# ManitoBoardFinal.net
KiCad netlist of a schematic drawn in EAGLE
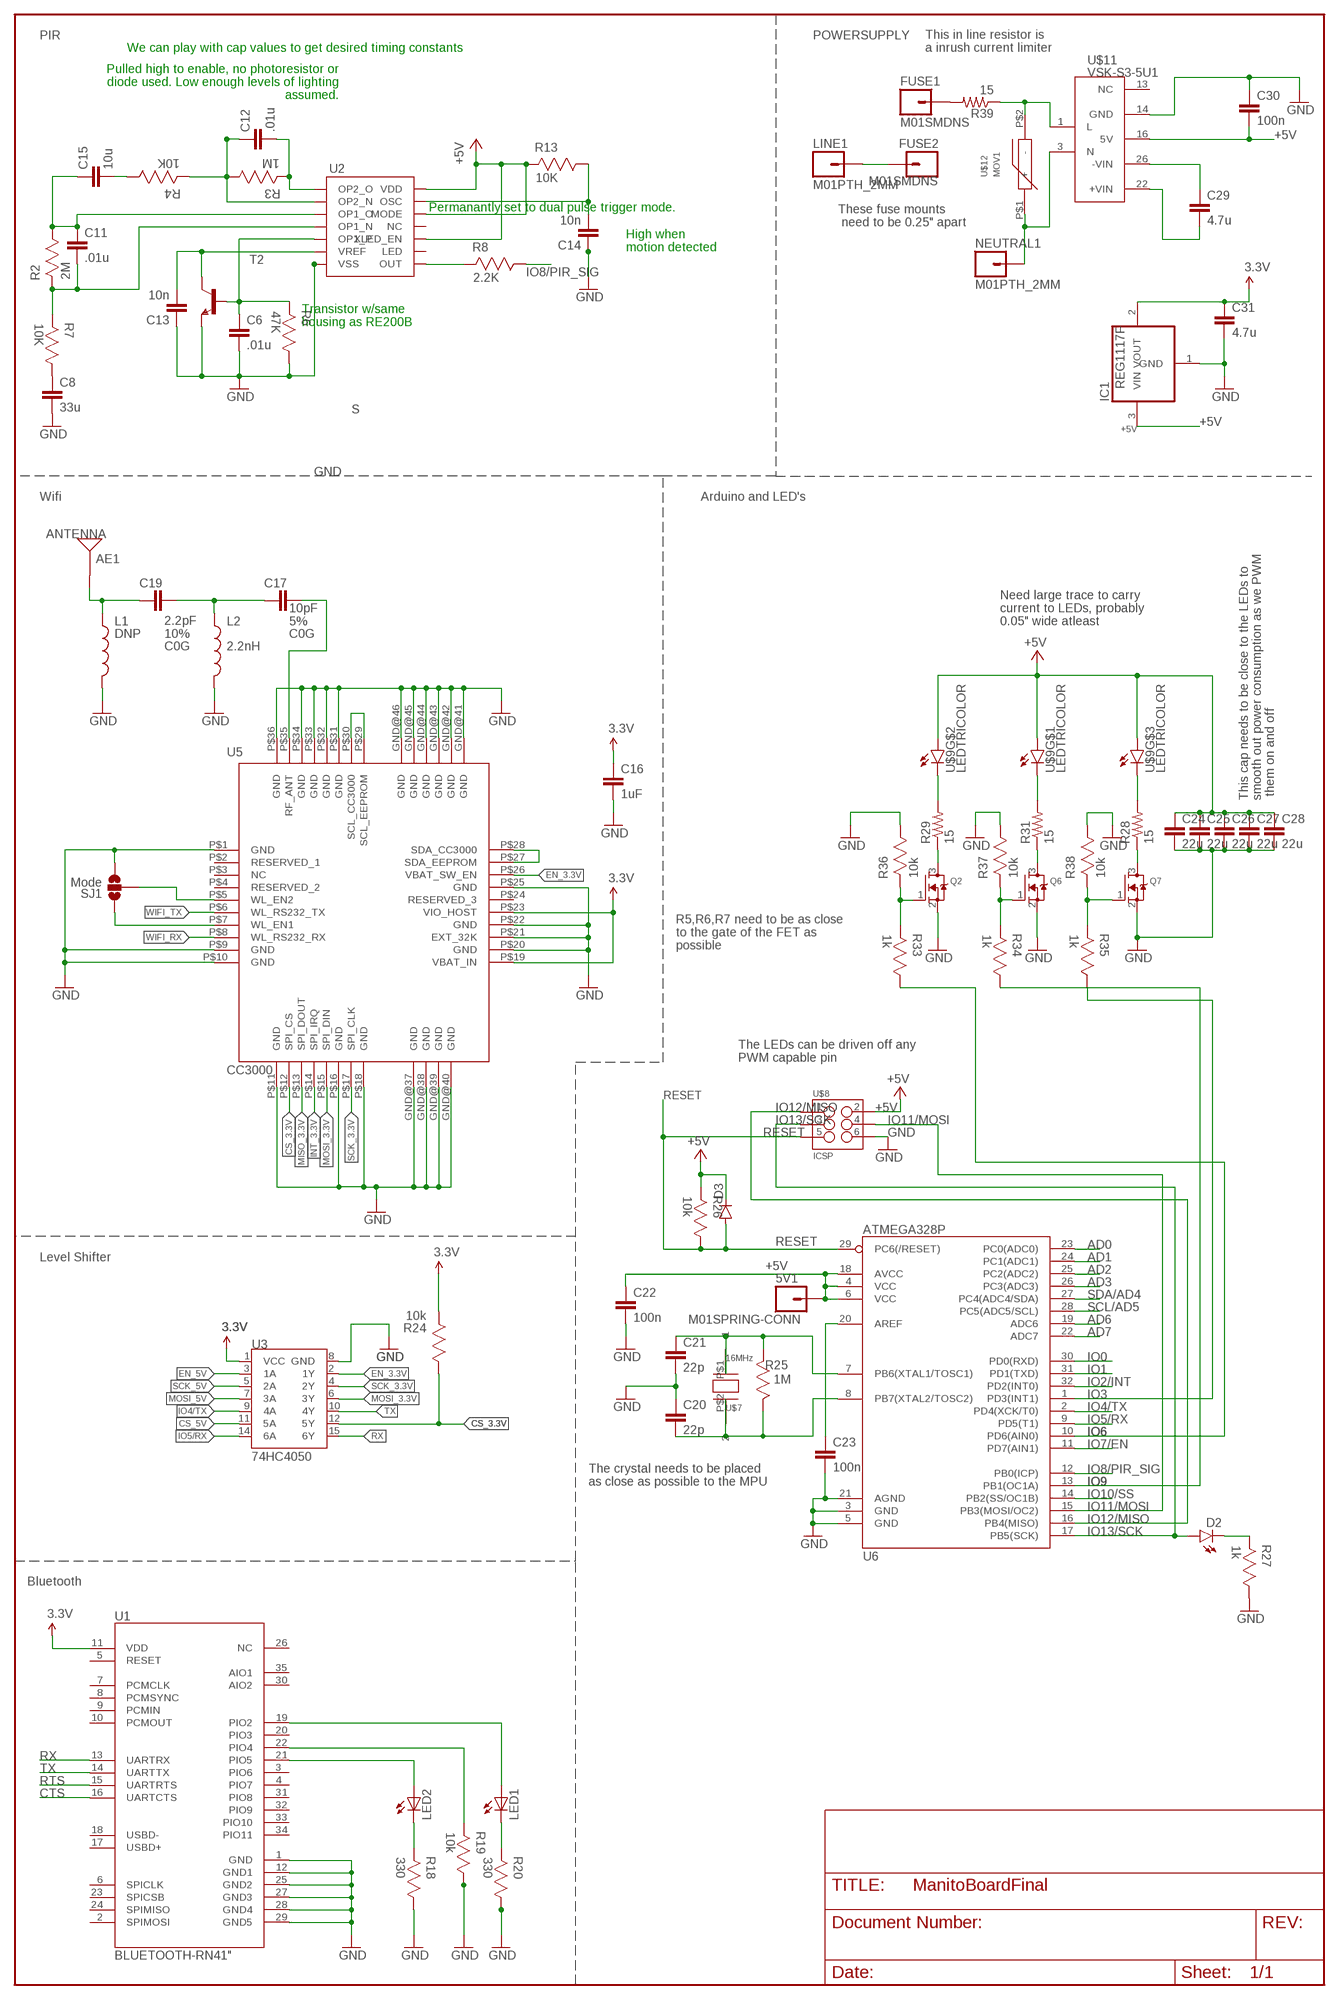
[diagram p0: schematic, sheet 1]

(export (version "E")
  (design (tool "Eeschema 10.0.6"))
  (components
    (comp (ref "5V1")
      (value "M01SPRING-CONN")
      (footprint "eagle-import:SPRING-CONNECTOR")
      (libsource (lib "eagle-import") (part "M01SPRING-CONN"))
    )
    (comp (ref "AE1")
      (value "ANTENNA")
      (footprint "eagle-import:ANTENNA-CHIP_2500AT44M0400")
      (libsource (lib "eagle-import") (part "ANTENNA22500AT44M0400"))
    )
    (comp (ref "C6")
      (value ".01u")
      (footprint "eagle-import:0805")
      (libsource (lib "eagle-import") (part "CAP0805"))
    )
    (comp (ref "C8")
      (value "33u")
      (footprint "eagle-import:0805")
      (libsource (lib "eagle-import") (part "CAP0805"))
    )
    (comp (ref "C11")
      (value ".01u")
      (footprint "eagle-import:0805")
      (libsource (lib "eagle-import") (part "CAP0805"))
    )
    (comp (ref "C12")
      (value ".01u")
      (footprint "eagle-import:0805")
      (libsource (lib "eagle-import") (part "CAP0805"))
    )
    (comp (ref "C13")
      (value "10n")
      (footprint "eagle-import:0805")
      (libsource (lib "eagle-import") (part "CAP0805"))
    )
    (comp (ref "C14")
      (value "10n")
      (footprint "eagle-import:0805")
      (libsource (lib "eagle-import") (part "CAP0805"))
    )
    (comp (ref "C15")
      (value "10u")
      (footprint "eagle-import:0805")
      (libsource (lib "eagle-import") (part "CAP0805"))
    )
    (comp (ref "C16")
      (value "1uF")
      (footprint "eagle-import:0805")
      (libsource (lib "eagle-import") (part "SparkFun-Capacitors_CAP0805"))
    )
    (comp (ref "C17")
      (value "10pF")
      (footprint "eagle-import:0603-CAP")
      (fields (field (name "COEFF") "C0G") (field (name "TOL") "5%"))
      (libsource (lib "eagle-import") (part "SparkFun-Capacitors_CAP0603-CAP"))
    )
    (comp (ref "C19")
      (value "2.2pF")
      (footprint "eagle-import:0603-CAP")
      (fields (field (name "COEFF") "C0G") (field (name "TOL") "10%"))
      (libsource (lib "eagle-import") (part "SparkFun-Capacitors_CAP0603-CAP"))
    )
    (comp (ref "C20")
      (value "22p")
      (footprint "eagle-import:0603-CAP")
      (libsource (lib "eagle-import") (part "CAP0603-CAP"))
    )
    (comp (ref "C21")
      (value "22p")
      (footprint "eagle-import:0603-CAP")
      (libsource (lib "eagle-import") (part "CAP0603-CAP"))
    )
    (comp (ref "C22")
      (value "100n")
      (footprint "eagle-import:0603-CAP")
      (libsource (lib "eagle-import") (part "CAP0603-CAP"))
    )
    (comp (ref "C23")
      (value "100n")
      (footprint "eagle-import:0603-CAP")
      (libsource (lib "eagle-import") (part "CAP0603-CAP"))
    )
    (comp (ref "C24")
      (value "22u")
      (footprint "eagle-import:0603-CAP")
      (libsource (lib "eagle-import") (part "CAP0603-CAP"))
    )
    (comp (ref "C25")
      (value "22u")
      (footprint "eagle-import:0603-CAP")
      (libsource (lib "eagle-import") (part "CAP0603-CAP"))
    )
    (comp (ref "C26")
      (value "22u")
      (footprint "eagle-import:0603-CAP")
      (libsource (lib "eagle-import") (part "CAP0603-CAP"))
    )
    (comp (ref "C27")
      (value "22u")
      (footprint "eagle-import:0603-CAP")
      (libsource (lib "eagle-import") (part "CAP0603-CAP"))
    )
    (comp (ref "C28")
      (value "22u")
      (footprint "eagle-import:0603-CAP")
      (libsource (lib "eagle-import") (part "CAP0603-CAP"))
    )
    (comp (ref "C29")
      (value "4.7u")
      (footprint "eagle-import:AXIAL-5MM")
      (libsource (lib "eagle-import") (part "CAP_"))
    )
    (comp (ref "C30")
      (value "100n")
      (footprint "eagle-import:0603-CAP")
      (libsource (lib "eagle-import") (part "CAP0603-CAP"))
    )
    (comp (ref "C31")
      (value "4.7u")
      (footprint "eagle-import:0603-CAP")
      (libsource (lib "eagle-import") (part "CAP0603-CAP"))
    )
    (comp (ref "D2")
      (value "LED-YELLOW0603")
      (footprint "eagle-import:LED-0603")
      (libsource (lib "eagle-import") (part "LED-YELLOW0603"))
    )
    (comp (ref "D3")
      (value "DIODESOD123")
      (footprint "eagle-import:SOD-123")
      (libsource (lib "eagle-import") (part "DIODESOD123"))
    )
    (comp (ref "FUSE1")
      (value "M01SMDNS")
      (footprint "eagle-import:1X01NS")
      (libsource (lib "eagle-import") (part "M01SMDNS"))
    )
    (comp (ref "FUSE2")
      (value "M01SMDNS")
      (footprint "eagle-import:1X01NS")
      (libsource (lib "eagle-import") (part "M01SMDNS"))
    )
    (comp (ref "IC1")
      (value "REG1117F")
      (footprint "eagle-import:DD-3")
      (fields (field (name "MF") "TEXAS INSTRUMENTS") (field (name "MPN") "REG1117FAKTTT"))
      (libsource (lib "eagle-import") (part "REG1117F"))
    )
    (comp (ref "L1")
      (value "DNP")
      (footprint "eagle-import:0603")
      (libsource (lib "eagle-import") (part "INDUCTOR0603"))
    )
    (comp (ref "L2")
      (value "2.2nH")
      (footprint "eagle-import:0603")
      (libsource (lib "eagle-import") (part "INDUCTOR0603"))
    )
    (comp (ref "LED1")
      (value "LED_ESML0603")
      (footprint "eagle-import:LED_SML0603")
      (libsource (lib "eagle-import") (part "LED_ESML0603"))
    )
    (comp (ref "LED2")
      (value "LED_ESML0603")
      (footprint "eagle-import:LED_SML0603")
      (libsource (lib "eagle-import") (part "LED_ESML0603"))
    )
    (comp (ref "LINE1")
      (value "M01PTH_2MM")
      (footprint "eagle-import:1X01_2MM")
      (libsource (lib "eagle-import") (part "M01PTH_2MM"))
    )
    (comp (ref "NEUTRAL1")
      (value "M01PTH_2MM")
      (footprint "eagle-import:1X01_2MM")
      (libsource (lib "eagle-import") (part "M01PTH_2MM"))
    )
    (comp (ref "Q2")
      (value "MOSFET-NREFLOW")
      (footprint "eagle-import:SOT23")
      (libsource (lib "eagle-import") (part "MOSFET-NREFLOW"))
    )
    (comp (ref "Q6")
      (value "MOSFET-NREFLOW")
      (footprint "eagle-import:SOT23")
      (libsource (lib "eagle-import") (part "MOSFET-NREFLOW"))
    )
    (comp (ref "Q7")
      (value "MOSFET-NREFLOW")
      (footprint "eagle-import:SOT23")
      (libsource (lib "eagle-import") (part "MOSFET-NREFLOW"))
    )
    (comp (ref "R2")
      (value "2M")
      (footprint "eagle-import:0603RESISTOR")
      (fields (field (name "MPN") "CRCW06031K21FKEA") (field (name "TOLERANCE") "± 1.0 %"))
      (libsource (lib "eagle-import") (part "0603RESISTOR1"))
    )
    (comp (ref "R3")
      (value "1M")
      (footprint "eagle-import:0603RESISTOR")
      (fields (field (name "MPN") "CRCW06031K21FKEA") (field (name "TOLERANCE") "± 1.0 %"))
      (libsource (lib "eagle-import") (part "0603RESISTOR1"))
    )
    (comp (ref "R4")
      (value "10K")
      (footprint "eagle-import:0603RESISTOR")
      (fields (field (name "MPN") "CRCW06031K21FKEA") (field (name "TOLERANCE") "± 1.0 %"))
      (libsource (lib "eagle-import") (part "0603RESISTOR1"))
    )
    (comp (ref "R6")
      (value "47K")
      (footprint "eagle-import:0603RESISTOR")
      (fields (field (name "MPN") "CRCW06031K21FKEA") (field (name "TOLERANCE") "± 1.0 %"))
      (libsource (lib "eagle-import") (part "0603RESISTOR1"))
    )
    (comp (ref "R7")
      (value "10K")
      (footprint "eagle-import:0603RESISTOR")
      (fields (field (name "MPN") "CRCW06031K21FKEA") (field (name "TOLERANCE") "± 1.0 %"))
      (libsource (lib "eagle-import") (part "0603RESISTOR1"))
    )
    (comp (ref "R8")
      (value "2.2K")
      (footprint "eagle-import:0603RESISTOR")
      (fields (field (name "MPN") "CRCW06031K21FKEA") (field (name "TOLERANCE") "± 1.0 %"))
      (libsource (lib "eagle-import") (part "0603RESISTOR1"))
    )
    (comp (ref "R13")
      (value "10K")
      (footprint "eagle-import:0603RESISTOR")
      (fields (field (name "MPN") "CRCW06031K21FKEA") (field (name "TOLERANCE") "± 1.0 %"))
      (libsource (lib "eagle-import") (part "0603RESISTOR1"))
    )
    (comp (ref "R18")
      (value "330")
      (footprint "eagle-import:0603RESISTOR")
      (fields (field (name "MPN") "CRCW06031K21FKEA") (field (name "TOLERANCE") "± 1.0 %"))
      (libsource (lib "eagle-import") (part "0603RESISTOR1"))
    )
    (comp (ref "R19")
      (value "10k")
      (footprint "eagle-import:0603RESISTOR")
      (fields (field (name "MPN") "CRCW06031K21FKEA") (field (name "TOLERANCE") "± 1.0 %"))
      (libsource (lib "eagle-import") (part "0603RESISTOR1"))
    )
    (comp (ref "R20")
      (value "330")
      (footprint "eagle-import:0603RESISTOR")
      (fields (field (name "MPN") "CRCW06031K21FKEA") (field (name "TOLERANCE") "± 1.0 %"))
      (libsource (lib "eagle-import") (part "0603RESISTOR1"))
    )
    (comp (ref "R24")
      (value "10k")
      (footprint "eagle-import:0603RESISTOR")
      (fields (field (name "MPN") "CRCW06031K21FKEA") (field (name "TOLERANCE") "± 1.0 %"))
      (libsource (lib "eagle-import") (part "0603RESISTOR1"))
    )
    (comp (ref "R25")
      (value "1M")
      (footprint "eagle-import:0603RESISTOR")
      (fields (field (name "MPN") "CRCW06031K21FKEA") (field (name "TOLERANCE") "± 1.0 %"))
      (libsource (lib "eagle-import") (part "0603RESISTOR1"))
    )
    (comp (ref "R26")
      (value "10k")
      (footprint "eagle-import:0603RESISTOR")
      (fields (field (name "MPN") "CRCW06031K21FKEA") (field (name "TOLERANCE") "± 1.0 %"))
      (libsource (lib "eagle-import") (part "0603RESISTOR1"))
    )
    (comp (ref "R27")
      (value "1k")
      (footprint "eagle-import:0603RESISTOR")
      (fields (field (name "MPN") "CRCW06031K21FKEA") (field (name "TOLERANCE") "± 1.0 %"))
      (libsource (lib "eagle-import") (part "0603RESISTOR1"))
    )
    (comp (ref "R28")
      (value "15")
      (footprint "eagle-import:AXIAL-0.6")
      (libsource (lib "eagle-import") (part "RESISTORPTH-1W"))
    )
    (comp (ref "R29")
      (value "15")
      (footprint "eagle-import:AXIAL-0.6")
      (libsource (lib "eagle-import") (part "RESISTORPTH-1W"))
    )
    (comp (ref "R31")
      (value "15")
      (footprint "eagle-import:AXIAL-0.6")
      (libsource (lib "eagle-import") (part "RESISTORPTH-1W"))
    )
    (comp (ref "R33")
      (value "1k")
      (footprint "eagle-import:0603RESISTOR")
      (fields (field (name "MPN") "CRCW06031K21FKEA") (field (name "TOLERANCE") "± 1.0 %"))
      (libsource (lib "eagle-import") (part "0603RESISTOR1"))
    )
    (comp (ref "R34")
      (value "1k")
      (footprint "eagle-import:0603RESISTOR")
      (fields (field (name "MPN") "CRCW06031K21FKEA") (field (name "TOLERANCE") "± 1.0 %"))
      (libsource (lib "eagle-import") (part "0603RESISTOR1"))
    )
    (comp (ref "R35")
      (value "1k")
      (footprint "eagle-import:0603RESISTOR")
      (fields (field (name "MPN") "CRCW06031K21FKEA") (field (name "TOLERANCE") "± 1.0 %"))
      (libsource (lib "eagle-import") (part "0603RESISTOR1"))
    )
    (comp (ref "R36")
      (value "10k")
      (footprint "eagle-import:0603RESISTOR")
      (fields (field (name "MPN") "CRCW06031K21FKEA") (field (name "TOLERANCE") "± 1.0 %"))
      (libsource (lib "eagle-import") (part "0603RESISTOR1"))
    )
    (comp (ref "R37")
      (value "10k")
      (footprint "eagle-import:0603RESISTOR")
      (fields (field (name "MPN") "CRCW06031K21FKEA") (field (name "TOLERANCE") "± 1.0 %"))
      (libsource (lib "eagle-import") (part "0603RESISTOR1"))
    )
    (comp (ref "R38")
      (value "10k")
      (footprint "eagle-import:0603RESISTOR")
      (fields (field (name "MPN") "CRCW06031K21FKEA") (field (name "TOLERANCE") "± 1.0 %"))
      (libsource (lib "eagle-import") (part "0603RESISTOR1"))
    )
    (comp (ref "R39")
      (value "15")
      (footprint "eagle-import:AXIAL-0.6")
      (libsource (lib "eagle-import") (part "RESISTORPTH-1W"))
    )
    (comp (ref "SJ1")
      (value "Mode")
      (footprint "eagle-import:SJ_3_PASTE1&2")
      (libsource (lib "eagle-import") (part "SOLDERJUMPER_2WAYPASTE1&2"))
    )
    (comp (ref "T2")
      (value "-NPN-TO5")
      (footprint "eagle-import:TO5")
      (libsource (lib "eagle-import") (part "-NPN-TO5"))
    )
    (comp (ref "U$7")
      (value "16MHz")
      (footprint "eagle-import:SMDCRYSTAL")
      (libsource (lib "eagle-import") (part "SMDCRYSTAL"))
    )
    (comp (ref "U$8")
      (value "ICSP")
      (footprint "eagle-import:2X3-ICSP")
      (libsource (lib "eagle-import") (part "6PIN-ICSP"))
    )
    (comp (ref "U$9")
      (value "LEDTRICOLOR")
      (footprint "eagle-import:TRICOLORLED")
      (libsource (lib "eagle-import") (part "LEDTRICOLOR"))
    )
    (comp (ref "U$11")
      (value "VSK-S3-5U1")
      (footprint "eagle-import:VSK-S3-DCAC")
      (libsource (lib "eagle-import") (part "VSK-S3-5U1"))
    )
    (comp (ref "U$12")
      (value "MOV1")
      (footprint "eagle-import:MOV")
      (libsource (lib "eagle-import") (part "MOV1"))
    )
    (comp (ref "U1")
      (value "BLUETOOTH-RN41\"")
      (footprint "eagle-import:RN41")
      (libsource (lib "eagle-import") (part "BLUETOOTH-RN41{dblquote}"))
    )
    (comp (ref "U2")
      (value "NCS36000")
      (footprint "eagle-import:SO14")
      (libsource (lib "eagle-import") (part "NCS36000"))
    )
    (comp (ref "U3")
      (value "74HC4050")
      (footprint "eagle-import:SO016")
      (libsource (lib "eagle-import") (part "HEX_CONVERTER"))
    )
    (comp (ref "U5")
      (value "CC3000")
      (footprint "eagle-import:QFN-46_CC3000")
      (libsource (lib "eagle-import") (part "CC3000"))
    )
    (comp (ref "U6")
      (value "ATMEGA328P")
      (footprint "eagle-import:TQFP32-08")
      (libsource (lib "eagle-import") (part "ATMEGA328_SMT"))
    )
  )
  (nets
    (net (code "1") (name "+5V") (class "Default")
      (node (ref "5V1") (pin "P$2") (pinfunction "1_P$2") (pintype "passive"))
      (node (ref "C22") (pin "1") (pinfunction "1_1") (pintype "passive"))
      (node (ref "C24") (pin "1") (pinfunction "1_1") (pintype "passive"))
      (node (ref "C25") (pin "1") (pinfunction "1_1") (pintype "passive"))
      (node (ref "C26") (pin "1") (pinfunction "1_1") (pintype "passive"))
      (node (ref "C27") (pin "1") (pinfunction "1_1") (pintype "passive"))
      (node (ref "C28") (pin "1") (pinfunction "1_1") (pintype "passive"))
      (node (ref "C30") (pin "2") (pinfunction "2_2") (pintype "passive"))
      (node (ref "D3") (pin "C") (pinfunction "C_C") (pintype "passive"))
      (node (ref "IC1") (pin "3") (pinfunction "VIN_3") (pintype "input"))
      (node (ref "R13") (pin "2") (pinfunction "2_2") (pintype "passive"))
      (node (ref "R26") (pin "2") (pinfunction "2_2") (pintype "passive"))
      (node (ref "U$11") (pin "16") (pinfunction "5V_16") (pintype "bidirectional"))
      (node (ref "U$8") (pin "2") (pinfunction "+5V_2") (pintype "power_in"))
      (node (ref "U$9") (pin "A1") (pinfunction "A_A1") (pintype "passive"))
      (node (ref "U$9") (pin "A2") (pinfunction "A_A2") (pintype "passive"))
      (node (ref "U$9") (pin "A3") (pinfunction "A_A3") (pintype "passive"))
      (node (ref "U2") (pin "10") (pinfunction "XLED_EN_10") (pintype "bidirectional"))
      (node (ref "U2") (pin "12") (pinfunction "MODE_12") (pintype "bidirectional"))
      (node (ref "U2") (pin "14") (pinfunction "VDD_14") (pintype "power_in"))
      (node (ref "U6") (pin "18") (pinfunction "AVCC_18") (pintype "bidirectional"))
      (node (ref "U6") (pin "4") (pinfunction "VCC_4") (pintype "bidirectional"))
      (node (ref "U6") (pin "6") (pinfunction "VCC_6") (pintype "bidirectional"))
    )
    (net (code "2") (name "/AD0") (class "Default")
      (node (ref "U6") (pin "23") (pinfunction "PC0(ADC0)_23") (pintype "bidirectional"))
    )
    (net (code "3") (name "/AD1") (class "Default")
      (node (ref "U6") (pin "24") (pinfunction "PC1(ADC1)_24") (pintype "bidirectional"))
    )
    (net (code "4") (name "/AD2") (class "Default")
      (node (ref "U6") (pin "25") (pinfunction "PC2(ADC2)_25") (pintype "bidirectional"))
    )
    (net (code "5") (name "/AD3") (class "Default")
      (node (ref "U6") (pin "26") (pinfunction "PC3(ADC3)_26") (pintype "bidirectional"))
    )
    (net (code "6") (name "/AD6") (class "Default")
      (node (ref "U6") (pin "19") (pinfunction "ADC6_19") (pintype "bidirectional"))
    )
    (net (code "7") (name "/AD7") (class "Default")
      (node (ref "U6") (pin "22") (pinfunction "ADC7_22") (pintype "bidirectional"))
    )
    (net (code "8") (name "/CTS") (class "Default")
      (node (ref "U1") (pin "16") (pinfunction "UARTCTS_16") (pintype "bidirectional"))
    )
    (net (code "9") (name "/IO0") (class "Default")
      (node (ref "U6") (pin "30") (pinfunction "PD0(RXD)_30") (pintype "bidirectional"))
    )
    (net (code "10") (name "/IO1") (class "Default")
      (node (ref "U6") (pin "31") (pinfunction "PD1(TXD)_31") (pintype "bidirectional"))
    )
    (net (code "11") (name "/IO2{slash}INT") (class "Default")
      (node (ref "U6") (pin "32") (pinfunction "PD2(INT0)_32") (pintype "bidirectional"))
    )
    (net (code "12") (name "/IO3") (class "Default")
      (node (ref "R35") (pin "1") (pinfunction "1_1") (pintype "passive"))
      (node (ref "U6") (pin "1") (pinfunction "PD3(INT1)_1") (pintype "bidirectional"))
    )
    (net (code "13") (name "/IO6") (class "Default")
      (node (ref "R33") (pin "1") (pinfunction "1_1") (pintype "passive"))
      (node (ref "U6") (pin "10") (pinfunction "PD6(AIN0)_10") (pintype "bidirectional"))
    )
    (net (code "14") (name "/IO7{slash}EN") (class "Default")
      (node (ref "U6") (pin "11") (pinfunction "PD7(AIN1)_11") (pintype "bidirectional"))
    )
    (net (code "15") (name "/IO8{slash}PIR_SIG") (class "Default")
      (node (ref "R8") (pin "1") (pinfunction "1_1") (pintype "passive"))
      (node (ref "U6") (pin "12") (pinfunction "PB0(ICP)_12") (pintype "bidirectional"))
    )
    (net (code "16") (name "/IO9") (class "Default")
      (node (ref "R34") (pin "1") (pinfunction "1_1") (pintype "passive"))
      (node (ref "U6") (pin "13") (pinfunction "PB1(OC1A)_13") (pintype "bidirectional"))
    )
    (net (code "17") (name "/IO10{slash}SS") (class "Default")
      (node (ref "U6") (pin "14") (pinfunction "PB2(SS/OC1B)_14") (pintype "bidirectional"))
    )
    (net (code "18") (name "/IO11{slash}MOSI") (class "Default")
      (node (ref "U$8") (pin "4") (pinfunction "MOSI_4") (pintype "bidirectional"))
      (node (ref "U6") (pin "15") (pinfunction "PB3(MOSI/OC2)_15") (pintype "bidirectional"))
    )
    (net (code "19") (name "/IO12{slash}MISO") (class "Default")
      (node (ref "U$8") (pin "1") (pinfunction "MISO_1") (pintype "bidirectional"))
      (node (ref "U6") (pin "16") (pinfunction "PB4(MISO)_16") (pintype "bidirectional"))
    )
    (net (code "20") (name "/IO13{slash}SCK") (class "Default")
      (node (ref "D2") (pin "A") (pinfunction "A_A") (pintype "passive"))
      (node (ref "U$8") (pin "3") (pinfunction "SCK_3") (pintype "bidirectional"))
      (node (ref "U6") (pin "17") (pinfunction "PB5(SCK)_17") (pintype "bidirectional"))
    )
    (net (code "22") (name "/RESET") (class "Default")
      (node (ref "D3") (pin "A") (pinfunction "A_A") (pintype "passive"))
      (node (ref "R26") (pin "1") (pinfunction "1_1") (pintype "passive"))
      (node (ref "U$8") (pin "5") (pinfunction "RESET_5") (pintype "bidirectional"))
      (node (ref "U6") (pin "29") (pinfunction "PC6(/RESET)_29") (pintype "bidirectional"))
    )
    (net (code "23") (name "/RTS") (class "Default")
      (node (ref "U1") (pin "15") (pinfunction "UARTRTS_15") (pintype "bidirectional"))
    )
    (net (code "24") (name "/S") (class "Default")
      (node (ref "C6") (pin "1") (pinfunction "1_1") (pintype "passive"))
      (node (ref "R6") (pin "2") (pinfunction "2_2") (pintype "passive"))
      (node (ref "T2") (pin "2") (pinfunction "B_2") (pintype "passive"))
      (node (ref "U2") (pin "5") (pinfunction "OP1_P_5") (pintype "bidirectional"))
    )
    (net (code "25") (name "/SCL{slash}AD5") (class "Default")
      (node (ref "U6") (pin "28") (pinfunction "PC5(ADC5/SCL)_28") (pintype "bidirectional"))
    )
    (net (code "26") (name "/SDA{slash}AD4") (class "Default")
      (node (ref "U6") (pin "27") (pinfunction "PC4(ADC4/SDA)_27") (pintype "bidirectional"))
    )
    (net (code "27") (name "3.3V") (class "Default")
      (node (ref "C16") (pin "1") (pinfunction "1_1") (pintype "passive"))
      (node (ref "C31") (pin "1") (pinfunction "1_1") (pintype "passive"))
      (node (ref "IC1") (pin "2") (pinfunction "VOUT_2") (pintype "output"))
      (node (ref "R24") (pin "2") (pinfunction "2_2") (pintype "passive"))
      (node (ref "U1") (pin "11") (pinfunction "VDD_11") (pintype "bidirectional"))
      (node (ref "U3") (pin "1") (pinfunction "VCC_1") (pintype "bidirectional"))
      (node (ref "U5") (pin "P$19") (pinfunction "VBAT_IN_P$19") (pintype "bidirectional"))
      (node (ref "U5") (pin "P$23") (pinfunction "VIO_HOST_P$23") (pintype "bidirectional"))
    )
    (net (code "28") (name "CS_3.3V") (class "Default")
      (node (ref "R24") (pin "1") (pinfunction "1_1") (pintype "passive"))
      (node (ref "U3") (pin "12") (pinfunction "5Y_12") (pintype "bidirectional"))
      (node (ref "U5") (pin "P$12") (pinfunction "SPI_CS_P$12") (pintype "bidirectional"))
    )
    (net (code "29") (name "CS_5V") (class "Default")
      (node (ref "U3") (pin "11") (pinfunction "5A_11") (pintype "bidirectional"))
    )
    (net (code "30") (name "EN_3.3V") (class "Default")
      (node (ref "U3") (pin "2") (pinfunction "1Y_2") (pintype "bidirectional"))
      (node (ref "U5") (pin "P$26") (pinfunction "VBAT_SW_EN_P$26") (pintype "bidirectional"))
    )
    (net (code "31") (name "EN_5V") (class "Default")
      (node (ref "U3") (pin "3") (pinfunction "1A_3") (pintype "bidirectional"))
    )
    (net (code "32") (name "GND") (class "Default")
      (node (ref "C13") (pin "1") (pinfunction "1_1") (pintype "passive"))
      (node (ref "C14") (pin "1") (pinfunction "1_1") (pintype "passive"))
      (node (ref "C16") (pin "2") (pinfunction "2_2") (pintype "passive"))
      (node (ref "C20") (pin "1") (pinfunction "1_1") (pintype "passive"))
      (node (ref "C21") (pin "2") (pinfunction "2_2") (pintype "passive"))
      (node (ref "C22") (pin "2") (pinfunction "2_2") (pintype "passive"))
      (node (ref "C23") (pin "2") (pinfunction "2_2") (pintype "passive"))
      (node (ref "C24") (pin "2") (pinfunction "2_2") (pintype "passive"))
      (node (ref "C25") (pin "2") (pinfunction "2_2") (pintype "passive"))
      (node (ref "C26") (pin "2") (pinfunction "2_2") (pintype "passive"))
      (node (ref "C27") (pin "2") (pinfunction "2_2") (pintype "passive"))
      (node (ref "C28") (pin "2") (pinfunction "2_2") (pintype "passive"))
      (node (ref "C30") (pin "1") (pinfunction "1_1") (pintype "passive"))
      (node (ref "C31") (pin "2") (pinfunction "2_2") (pintype "passive"))
      (node (ref "C6") (pin "2") (pinfunction "2_2") (pintype "passive"))
      (node (ref "C8") (pin "2") (pinfunction "2_2") (pintype "passive"))
      (node (ref "IC1") (pin "1") (pinfunction "GND_1") (pintype "power_in"))
      (node (ref "L1") (pin "2") (pinfunction "2_2") (pintype "passive"))
      (node (ref "L2") (pin "2") (pinfunction "2_2") (pintype "passive"))
      (node (ref "Q2") (pin "2") (pinfunction "S_2") (pintype "bidirectional"))
      (node (ref "Q6") (pin "2") (pinfunction "S_2") (pintype "bidirectional"))
      (node (ref "Q7") (pin "2") (pinfunction "S_2") (pintype "bidirectional"))
      (node (ref "R18") (pin "1") (pinfunction "1_1") (pintype "passive"))
      (node (ref "R19") (pin "1") (pinfunction "1_1") (pintype "passive"))
      (node (ref "R20") (pin "1") (pinfunction "1_1") (pintype "passive"))
      (node (ref "R27") (pin "1") (pinfunction "1_1") (pintype "passive"))
      (node (ref "R36") (pin "1") (pinfunction "1_1") (pintype "passive"))
      (node (ref "R37") (pin "1") (pinfunction "1_1") (pintype "passive"))
      (node (ref "R38") (pin "1") (pinfunction "1_1") (pintype "passive"))
      (node (ref "R6") (pin "1") (pinfunction "1_1") (pintype "passive"))
      (node (ref "SJ1") (pin "3") (pinfunction "3_3") (pintype "passive"))
      (node (ref "T2") (pin "1") (pinfunction "E_1") (pintype "passive"))
      (node (ref "U$11") (pin "14") (pinfunction "GND_14") (pintype "bidirectional"))
      (node (ref "U$8") (pin "6") (pinfunction "GND_6") (pintype "power_in"))
      (node (ref "U1") (pin "1") (pinfunction "GND_1") (pintype "bidirectional"))
      (node (ref "U1") (pin "12") (pinfunction "GND1_12") (pintype "bidirectional"))
      (node (ref "U1") (pin "25") (pinfunction "GND2_25") (pintype "bidirectional"))
      (node (ref "U1") (pin "27") (pinfunction "GND3_27") (pintype "bidirectional"))
      (node (ref "U1") (pin "28") (pinfunction "GND4_28") (pintype "bidirectional"))
      (node (ref "U1") (pin "29") (pinfunction "GND5_29") (pintype "bidirectional"))
      (node (ref "U2") (pin "7") (pinfunction "VSS_7") (pintype "power_in"))
      (node (ref "U3") (pin "8") (pinfunction "GND_8") (pintype "bidirectional"))
      (node (ref "U5") (pin "GND@37") (pinfunction "GND_GND@37") (pintype "bidirectional"))
      (node (ref "U5") (pin "GND@38") (pinfunction "GND_GND@38") (pintype "bidirectional"))
      (node (ref "U5") (pin "GND@39") (pinfunction "GND_GND@39") (pintype "bidirectional"))
      (node (ref "U5") (pin "GND@40") (pinfunction "GND_GND@40") (pintype "bidirectional"))
      (node (ref "U5") (pin "GND@41") (pinfunction "GND_GND@41") (pintype "bidirectional"))
      (node (ref "U5") (pin "GND@42") (pinfunction "GND_GND@42") (pintype "bidirectional"))
      (node (ref "U5") (pin "GND@43") (pinfunction "GND_GND@43") (pintype "bidirectional"))
      (node (ref "U5") (pin "GND@44") (pinfunction "GND_GND@44") (pintype "bidirectional"))
      (node (ref "U5") (pin "GND@45") (pinfunction "GND_GND@45") (pintype "bidirectional"))
      (node (ref "U5") (pin "GND@46") (pinfunction "GND_GND@46") (pintype "bidirectional"))
      (node (ref "U5") (pin "P$1") (pinfunction "GND_P$1") (pintype "bidirectional"))
      (node (ref "U5") (pin "P$10") (pinfunction "GND_P$10") (pintype "bidirectional"))
      (node (ref "U5") (pin "P$11") (pinfunction "GND_P$11") (pintype "bidirectional"))
      (node (ref "U5") (pin "P$16") (pinfunction "GND_P$16") (pintype "bidirectional"))
      (node (ref "U5") (pin "P$18") (pinfunction "GND_P$18") (pintype "bidirectional"))
      (node (ref "U5") (pin "P$20") (pinfunction "GND_P$20") (pintype "bidirectional"))
      (node (ref "U5") (pin "P$21") (pinfunction "EXT_32K_P$21") (pintype "bidirectional"))
      (node (ref "U5") (pin "P$22") (pinfunction "GND_P$22") (pintype "bidirectional"))
      (node (ref "U5") (pin "P$25") (pinfunction "GND_P$25") (pintype "bidirectional"))
      (node (ref "U5") (pin "P$31") (pinfunction "GND_P$31") (pintype "bidirectional"))
      (node (ref "U5") (pin "P$32") (pinfunction "GND_P$32") (pintype "bidirectional"))
      (node (ref "U5") (pin "P$33") (pinfunction "GND_P$33") (pintype "bidirectional"))
      (node (ref "U5") (pin "P$34") (pinfunction "GND_P$34") (pintype "bidirectional"))
      (node (ref "U5") (pin "P$36") (pinfunction "GND_P$36") (pintype "bidirectional"))
      (node (ref "U5") (pin "P$9") (pinfunction "GND_P$9") (pintype "bidirectional"))
      (node (ref "U6") (pin "21") (pinfunction "AGND_21") (pintype "bidirectional"))
      (node (ref "U6") (pin "3") (pinfunction "GND_3") (pintype "bidirectional"))
      (node (ref "U6") (pin "5") (pinfunction "GND_5") (pintype "bidirectional"))
    )
    (net (code "33") (name "INT_3.3V") (class "Default")
      (node (ref "U5") (pin "P$14") (pinfunction "SPI_IRQ_P$14") (pintype "bidirectional"))
    )
    (net (code "34") (name "IO4{slash}TX") (class "Default")
      (node (ref "U3") (pin "9") (pinfunction "4A_9") (pintype "bidirectional"))
      (node (ref "U6") (pin "2") (pinfunction "PD4(XCK/T0)_2") (pintype "bidirectional"))
    )
    (net (code "35") (name "IO5{slash}RX") (class "Default")
      (node (ref "U3") (pin "14") (pinfunction "6A_14") (pintype "bidirectional"))
      (node (ref "U6") (pin "9") (pinfunction "PD5(T1)_9") (pintype "bidirectional"))
    )
    (net (code "36") (name "MISO_3.3V") (class "Default")
      (node (ref "U5") (pin "P$13") (pinfunction "SPI_DOUT_P$13") (pintype "bidirectional"))
    )
    (net (code "37") (name "MOSI_3.3V") (class "Default")
      (node (ref "U3") (pin "6") (pinfunction "3Y_6") (pintype "bidirectional"))
      (node (ref "U5") (pin "P$15") (pinfunction "SPI_DIN_P$15") (pintype "bidirectional"))
    )
    (net (code "38") (name "MOSI_5V") (class "Default")
      (node (ref "U3") (pin "7") (pinfunction "3A_7") (pintype "bidirectional"))
    )
    (net (code "39") (name "Net-(AE1-SIGNAL)") (class "Default")
      (node (ref "AE1") (pin "FEED") (pinfunction "SIGNAL_FEED") (pintype "bidirectional"))
      (node (ref "C19") (pin "1") (pinfunction "1_1") (pintype "passive"))
      (node (ref "L1") (pin "1") (pinfunction "1_1") (pintype "passive"))
    )
    (net (code "40") (name "Net-(C8-Pad1)") (class "Default")
      (node (ref "C8") (pin "1") (pinfunction "1_1") (pintype "passive"))
      (node (ref "R7") (pin "1") (pinfunction "1_1") (pintype "passive"))
    )
    (net (code "41") (name "Net-(C15-Pad2)") (class "Default")
      (node (ref "C15") (pin "2") (pinfunction "2_2") (pintype "passive"))
      (node (ref "R4") (pin "1") (pinfunction "1_1") (pintype "passive"))
    )
    (net (code "42") (name "Net-(C17-Pad1)") (class "Default")
      (node (ref "C17") (pin "1") (pinfunction "1_1") (pintype "passive"))
      (node (ref "C19") (pin "2") (pinfunction "2_2") (pintype "passive"))
      (node (ref "L2") (pin "1") (pinfunction "1_1") (pintype "passive"))
    )
    (net (code "43") (name "Net-(C29-1)") (class "Default")
      (node (ref "C29") (pin "P$1") (pinfunction "1_P$1") (pintype "passive"))
      (node (ref "U$11") (pin "26") (pinfunction "-VIN_26") (pintype "bidirectional"))
    )
    (net (code "44") (name "Net-(C29-2)") (class "Default")
      (node (ref "C29") (pin "P$2") (pinfunction "2_P$2") (pintype "passive"))
      (node (ref "U$11") (pin "22") (pinfunction "+VIN_22") (pintype "bidirectional"))
    )
    (net (code "45") (name "Net-(D2-PadC)") (class "Default")
      (node (ref "D2") (pin "C") (pinfunction "C_C") (pintype "passive"))
      (node (ref "R27") (pin "2") (pinfunction "2_2") (pintype "passive"))
    )
    (net (code "46") (name "Net-(FUSE2-Pad1)") (class "Default")
      (node (ref "FUSE2") (pin "1") (pinfunction "1_1") (pintype "passive"))
      (node (ref "LINE1") (pin "1") (pinfunction "1_1") (pintype "passive"))
    )
    (net (code "47") (name "Net-(LED1-PadC)") (class "Default")
      (node (ref "LED1") (pin "C") (pinfunction "C_C") (pintype "passive"))
      (node (ref "R20") (pin "2") (pinfunction "2_2") (pintype "passive"))
    )
    (net (code "48") (name "Net-(LED2-PadC)") (class "Default")
      (node (ref "LED2") (pin "C") (pinfunction "C_C") (pintype "passive"))
      (node (ref "R18") (pin "2") (pinfunction "2_2") (pintype "passive"))
    )
    (net (code "49") (name "Net-(Q2-D)") (class "Default")
      (node (ref "Q2") (pin "3") (pinfunction "D_3") (pintype "bidirectional"))
      (node (ref "R29") (pin "P$1") (pinfunction "1_P$1") (pintype "passive"))
    )
    (net (code "50") (name "Net-(Q2-G)") (class "Default")
      (node (ref "Q2") (pin "1") (pinfunction "G_1") (pintype "bidirectional"))
      (node (ref "R33") (pin "2") (pinfunction "2_2") (pintype "passive"))
      (node (ref "R36") (pin "2") (pinfunction "2_2") (pintype "passive"))
    )
    (net (code "51") (name "Net-(Q6-D)") (class "Default")
      (node (ref "Q6") (pin "3") (pinfunction "D_3") (pintype "bidirectional"))
      (node (ref "R31") (pin "P$1") (pinfunction "1_P$1") (pintype "passive"))
    )
    (net (code "52") (name "Net-(Q6-G)") (class "Default")
      (node (ref "Q6") (pin "1") (pinfunction "G_1") (pintype "bidirectional"))
      (node (ref "R34") (pin "2") (pinfunction "2_2") (pintype "passive"))
      (node (ref "R37") (pin "2") (pinfunction "2_2") (pintype "passive"))
    )
    (net (code "53") (name "Net-(Q7-D)") (class "Default")
      (node (ref "Q7") (pin "3") (pinfunction "D_3") (pintype "bidirectional"))
      (node (ref "R28") (pin "P$1") (pinfunction "1_P$1") (pintype "passive"))
    )
    (net (code "54") (name "Net-(Q7-G)") (class "Default")
      (node (ref "Q7") (pin "1") (pinfunction "G_1") (pintype "bidirectional"))
      (node (ref "R35") (pin "2") (pinfunction "2_2") (pintype "passive"))
      (node (ref "R38") (pin "2") (pinfunction "2_2") (pintype "passive"))
    )
    (net (code "55") (name "Net-(R28-2)") (class "Default")
      (node (ref "R28") (pin "P$2") (pinfunction "2_P$2") (pintype "passive"))
      (node (ref "U$9") (pin "C3") (pinfunction "C_C3") (pintype "passive"))
    )
    (net (code "56") (name "Net-(R29-2)") (class "Default")
      (node (ref "R29") (pin "P$2") (pinfunction "2_P$2") (pintype "passive"))
      (node (ref "U$9") (pin "C2") (pinfunction "C_C2") (pintype "passive"))
    )
    (net (code "57") (name "Net-(R31-2)") (class "Default")
      (node (ref "R31") (pin "P$2") (pinfunction "2_P$2") (pintype "passive"))
      (node (ref "U$9") (pin "C1") (pinfunction "C_C1") (pintype "passive"))
    )
    (net (code "58") (name "Net-(R39-1)") (class "Default")
      (node (ref "R39") (pin "P$1") (pinfunction "1_P$1") (pintype "passive"))
      (node (ref "U$11") (pin "1") (pinfunction "L_1") (pintype "bidirectional"))
      (node (ref "U$12") (pin "P$2") (pinfunction "-_P$2") (pintype "bidirectional"))
    )
    (net (code "59") (name "Net-(R39-2)") (class "Default")
      (node (ref "FUSE1") (pin "1") (pinfunction "1_1") (pintype "passive"))
      (node (ref "R39") (pin "P$2") (pinfunction "2_P$2") (pintype "passive"))
    )
    (net (code "60") (name "Net-(T2-C)") (class "Default")
      (node (ref "C13") (pin "2") (pinfunction "2_2") (pintype "passive"))
      (node (ref "T2") (pin "3") (pinfunction "C_3") (pintype "passive"))
      (node (ref "U2") (pin "6") (pinfunction "VREF_6") (pintype "power_in"))
    )
    (net (code "61") (name "Net-(U$7-1)") (class "Default")
      (node (ref "C21") (pin "1") (pinfunction "1_1") (pintype "passive"))
      (node (ref "R25") (pin "2") (pinfunction "2_2") (pintype "passive"))
      (node (ref "U$7") (pin "P$1") (pinfunction "1_P$1") (pintype "bidirectional"))
      (node (ref "U6") (pin "7") (pinfunction "PB6(XTAL1/TOSC1)_7") (pintype "bidirectional"))
    )
    (net (code "62") (name "Net-(U$7-2)") (class "Default")
      (node (ref "C20") (pin "2") (pinfunction "2_2") (pintype "passive"))
      (node (ref "R25") (pin "1") (pinfunction "1_1") (pintype "passive"))
      (node (ref "U$7") (pin "P$2") (pinfunction "2_P$2") (pintype "bidirectional"))
      (node (ref "U6") (pin "8") (pinfunction "PB7(XTAL2/TOSC2)_8") (pintype "bidirectional"))
    )
    (net (code "63") (name "Net-(U$11-N)") (class "Default")
      (node (ref "NEUTRAL1") (pin "1") (pinfunction "1_1") (pintype "passive"))
      (node (ref "U$11") (pin "3") (pinfunction "N_3") (pintype "bidirectional"))
      (node (ref "U$12") (pin "P$1") (pinfunction "+_P$1") (pintype "bidirectional"))
    )
    (net (code "64") (name "Net-(U1-PIO2)") (class "Default")
      (node (ref "LED1") (pin "A") (pinfunction "A_A") (pintype "passive"))
      (node (ref "U1") (pin "19") (pinfunction "PIO2_19") (pintype "bidirectional"))
    )
    (net (code "65") (name "Net-(U1-PIO4)") (class "Default")
      (node (ref "R19") (pin "2") (pinfunction "2_2") (pintype "passive"))
      (node (ref "U1") (pin "22") (pinfunction "PIO4_22") (pintype "bidirectional"))
    )
    (net (code "66") (name "Net-(U1-PIO5)") (class "Default")
      (node (ref "LED2") (pin "A") (pinfunction "A_A") (pintype "passive"))
      (node (ref "U1") (pin "21") (pinfunction "PIO5_21") (pintype "bidirectional"))
    )
    (net (code "67") (name "Net-(U2-OP1_N)") (class "Default")
      (node (ref "C11") (pin "2") (pinfunction "2_2") (pintype "passive"))
      (node (ref "R2") (pin "2") (pinfunction "2_2") (pintype "passive"))
      (node (ref "R7") (pin "2") (pinfunction "2_2") (pintype "passive"))
      (node (ref "U2") (pin "4") (pinfunction "OP1_N_4") (pintype "bidirectional"))
    )
    (net (code "68") (name "Net-(U2-OP1_O)") (class "Default")
      (node (ref "C11") (pin "1") (pinfunction "1_1") (pintype "passive"))
      (node (ref "C15") (pin "1") (pinfunction "1_1") (pintype "passive"))
      (node (ref "R2") (pin "1") (pinfunction "1_1") (pintype "passive"))
      (node (ref "U2") (pin "3") (pinfunction "OP1_O_3") (pintype "bidirectional"))
    )
    (net (code "69") (name "Net-(U2-OP2_N)") (class "Default")
      (node (ref "C12") (pin "1") (pinfunction "1_1") (pintype "passive"))
      (node (ref "R3") (pin "1") (pinfunction "1_1") (pintype "passive"))
      (node (ref "R4") (pin "2") (pinfunction "2_2") (pintype "passive"))
      (node (ref "U2") (pin "2") (pinfunction "OP2_N_2") (pintype "bidirectional"))
    )
    (net (code "70") (name "Net-(U2-OP2_O)") (class "Default")
      (node (ref "C12") (pin "2") (pinfunction "2_2") (pintype "passive"))
      (node (ref "R3") (pin "2") (pinfunction "2_2") (pintype "passive"))
      (node (ref "U2") (pin "1") (pinfunction "OP2_O_1") (pintype "bidirectional"))
    )
    (net (code "71") (name "Net-(U2-OSC)") (class "Default")
      (node (ref "C14") (pin "2") (pinfunction "2_2") (pintype "passive"))
      (node (ref "R13") (pin "1") (pinfunction "1_1") (pintype "passive"))
      (node (ref "U2") (pin "13") (pinfunction "OSC_13") (pintype "bidirectional"))
    )
    (net (code "72") (name "Net-(U2-OUT)") (class "Default")
      (node (ref "R8") (pin "2") (pinfunction "2_2") (pintype "passive"))
      (node (ref "U2") (pin "8") (pinfunction "OUT_8") (pintype "bidirectional"))
    )
    (net (code "73") (name "Net-(U5-RF_ANT)") (class "Default")
      (node (ref "C17") (pin "2") (pinfunction "2_2") (pintype "passive"))
      (node (ref "U5") (pin "P$35") (pinfunction "RF_ANT_P$35") (pintype "bidirectional"))
    )
    (net (code "74") (name "Net-(U5-SCL_CC3000)") (class "Default")
      (node (ref "U5") (pin "P$29") (pinfunction "SCL_EEPROM_P$29") (pintype "bidirectional"))
      (node (ref "U5") (pin "P$30") (pinfunction "SCL_CC3000_P$30") (pintype "bidirectional"))
    )
    (net (code "75") (name "Net-(U5-SDA_CC3000)") (class "Default")
      (node (ref "U5") (pin "P$27") (pinfunction "SDA_EEPROM_P$27") (pintype "bidirectional"))
      (node (ref "U5") (pin "P$28") (pinfunction "SDA_CC3000_P$28") (pintype "bidirectional"))
    )
    (net (code "76") (name "Net-(U5-WL_EN1)") (class "Default")
      (node (ref "SJ1") (pin "1") (pinfunction "1_1") (pintype "passive"))
      (node (ref "U5") (pin "P$7") (pinfunction "WL_EN1_P$7") (pintype "bidirectional"))
    )
    (net (code "77") (name "Net-(U5-WL_EN2)") (class "Default")
      (node (ref "SJ1") (pin "2") (pinfunction "2_2") (pintype "passive"))
      (node (ref "U5") (pin "P$5") (pinfunction "WL_EN2_P$5") (pintype "bidirectional"))
    )
    (net (code "78") (name "Net-(U6-AREF)") (class "Default")
      (node (ref "C23") (pin "1") (pinfunction "1_1") (pintype "passive"))
      (node (ref "U6") (pin "20") (pinfunction "AREF_20") (pintype "bidirectional"))
    )
    (net (code "79") (name "RX") (class "Default")
      (node (ref "U1") (pin "13") (pinfunction "UARTRX_13") (pintype "bidirectional"))
      (node (ref "U3") (pin "15") (pinfunction "6Y_15") (pintype "bidirectional"))
    )
    (net (code "80") (name "SCK_3.3V") (class "Default")
      (node (ref "U3") (pin "4") (pinfunction "2Y_4") (pintype "bidirectional"))
      (node (ref "U5") (pin "P$17") (pinfunction "SPI_CLK_P$17") (pintype "bidirectional"))
    )
    (net (code "81") (name "SCK_5V") (class "Default")
      (node (ref "U3") (pin "5") (pinfunction "2A_5") (pintype "bidirectional"))
    )
    (net (code "82") (name "TX") (class "Default")
      (node (ref "U1") (pin "14") (pinfunction "UARTTX_14") (pintype "bidirectional"))
      (node (ref "U3") (pin "10") (pinfunction "4Y_10") (pintype "bidirectional"))
    )
    (net (code "83") (name "WIFI_RX") (class "Default")
      (node (ref "U5") (pin "P$8") (pinfunction "WL_RS232_RX_P$8") (pintype "bidirectional"))
    )
    (net (code "84") (name "WIFI_TX") (class "Default")
      (node (ref "U5") (pin "P$6") (pinfunction "WL_RS232_TX_P$6") (pintype "bidirectional"))
    )
    (net (code "85") (name "unconnected-(U$11-NC-Pad13)") (class "Default")
      (node (ref "U$11") (pin "13") (pinfunction "NC_13") (pintype "no_connect"))
    )
    (net (code "86") (name "unconnected-(U1-AIO1-Pad35)") (class "Default")
      (node (ref "U1") (pin "35") (pinfunction "AIO1_35") (pintype "bidirectional"))
    )
    (net (code "87") (name "unconnected-(U1-AIO2-Pad30)") (class "Default")
      (node (ref "U1") (pin "30") (pinfunction "AIO2_30") (pintype "bidirectional"))
    )
    (net (code "88") (name "unconnected-(U1-NC-Pad26)") (class "Default")
      (node (ref "U1") (pin "26") (pinfunction "NC_26") (pintype "bidirectional"))
    )
    (net (code "89") (name "unconnected-(U1-PCMCLK-Pad7)") (class "Default")
      (node (ref "U1") (pin "7") (pinfunction "PCMCLK_7") (pintype "bidirectional"))
    )
    (net (code "90") (name "unconnected-(U1-PCMIN-Pad9)") (class "Default")
      (node (ref "U1") (pin "9") (pinfunction "PCMIN_9") (pintype "bidirectional"))
    )
    (net (code "91") (name "unconnected-(U1-PCMOUT-Pad10)") (class "Default")
      (node (ref "U1") (pin "10") (pinfunction "PCMOUT_10") (pintype "bidirectional"))
    )
    (net (code "92") (name "unconnected-(U1-PCMSYNC-Pad8)") (class "Default")
      (node (ref "U1") (pin "8") (pinfunction "PCMSYNC_8") (pintype "bidirectional"))
    )
    (net (code "93") (name "unconnected-(U1-PIO3-Pad20)") (class "Default")
      (node (ref "U1") (pin "20") (pinfunction "PIO3_20") (pintype "bidirectional"))
    )
    (net (code "94") (name "unconnected-(U1-PIO6-Pad3)") (class "Default")
      (node (ref "U1") (pin "3") (pinfunction "PIO6_3") (pintype "bidirectional"))
    )
    (net (code "95") (name "unconnected-(U1-PIO7-Pad4)") (class "Default")
      (node (ref "U1") (pin "4") (pinfunction "PIO7_4") (pintype "bidirectional"))
    )
    (net (code "96") (name "unconnected-(U1-PIO8-Pad31)") (class "Default")
      (node (ref "U1") (pin "31") (pinfunction "PIO8_31") (pintype "bidirectional"))
    )
    (net (code "97") (name "unconnected-(U1-PIO9-Pad32)") (class "Default")
      (node (ref "U1") (pin "32") (pinfunction "PIO9_32") (pintype "bidirectional"))
    )
    (net (code "98") (name "unconnected-(U1-PIO10-Pad33)") (class "Default")
      (node (ref "U1") (pin "33") (pinfunction "PIO10_33") (pintype "bidirectional"))
    )
    (net (code "99") (name "unconnected-(U1-PIO11-Pad34)") (class "Default")
      (node (ref "U1") (pin "34") (pinfunction "PIO11_34") (pintype "bidirectional"))
    )
    (net (code "100") (name "unconnected-(U1-RESET-Pad5)") (class "Default")
      (node (ref "U1") (pin "5") (pinfunction "RESET_5") (pintype "bidirectional"))
    )
    (net (code "101") (name "unconnected-(U1-SPICLK-Pad6)") (class "Default")
      (node (ref "U1") (pin "6") (pinfunction "SPICLK_6") (pintype "bidirectional"))
    )
    (net (code "102") (name "unconnected-(U1-SPICSB-Pad23)") (class "Default")
      (node (ref "U1") (pin "23") (pinfunction "SPICSB_23") (pintype "bidirectional"))
    )
    (net (code "103") (name "unconnected-(U1-SPIMISO-Pad24)") (class "Default")
      (node (ref "U1") (pin "24") (pinfunction "SPIMISO_24") (pintype "bidirectional"))
    )
    (net (code "104") (name "unconnected-(U1-SPIMOSI-Pad2)") (class "Default")
      (node (ref "U1") (pin "2") (pinfunction "SPIMOSI_2") (pintype "bidirectional"))
    )
    (net (code "105") (name "unconnected-(U1-USBD+-Pad17)") (class "Default")
      (node (ref "U1") (pin "17") (pinfunction "USBD+_17") (pintype "bidirectional"))
    )
    (net (code "106") (name "unconnected-(U1-USBD--Pad18)") (class "Default")
      (node (ref "U1") (pin "18") (pinfunction "USBD-_18") (pintype "bidirectional"))
    )
    (net (code "107") (name "unconnected-(U2-LED-Pad9)") (class "Default")
      (node (ref "U2") (pin "9") (pinfunction "LED_9") (pintype "bidirectional"))
    )
    (net (code "108") (name "unconnected-(U2-NC-Pad11)") (class "Default")
      (node (ref "U2") (pin "11") (pinfunction "NC_11") (pintype "bidirectional"))
    )
    (net (code "109") (name "unconnected-(U5-NC-PadP$3)") (class "Default")
      (node (ref "U5") (pin "P$3") (pinfunction "NC_P$3") (pintype "bidirectional"))
    )
    (net (code "110") (name "unconnected-(U5-RESERVED_1-PadP$2)") (class "Default")
      (node (ref "U5") (pin "P$2") (pinfunction "RESERVED_1_P$2") (pintype "bidirectional"))
    )
    (net (code "111") (name "unconnected-(U5-RESERVED_2-PadP$4)") (class "Default")
      (node (ref "U5") (pin "P$4") (pinfunction "RESERVED_2_P$4") (pintype "bidirectional"))
    )
    (net (code "112") (name "unconnected-(U5-RESERVED_3-PadP$24)") (class "Default")
      (node (ref "U5") (pin "P$24") (pinfunction "RESERVED_3_P$24") (pintype "bidirectional"))
    )
  )
)
